# arduino.net
KiCad netlist of a schematic drawn in EAGLE
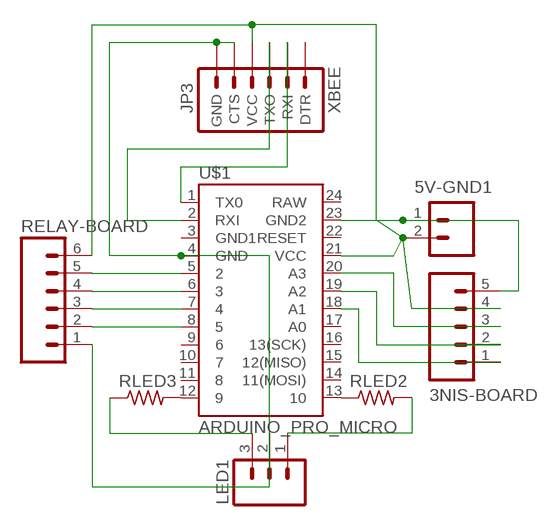
[diagram p0: schematic, sheet 1]

(export (version "E")
  (design (tool "Eeschema 10.0.6"))
  (components
    (comp (ref "3NIS-BOARD")
      (value "M05PTH")
      (footprint "eagle-import:1X05")
      (libsource (lib "eagle-import") (part "M05PTH"))
    )
    (comp (ref "5V-GND1")
      (value "M025MM")
      (footprint "eagle-import:SCREWTERMINAL-5MM-2")
      (libsource (lib "eagle-import") (part "M025MM"))
    )
    (comp (ref "JP3")
      (value "XBEE")
      (footprint "eagle-import:1X06")
      (libsource (lib "eagle-import") (part "ARDUINO_SERIAL_PROGRAMPTH"))
    )
    (comp (ref "LED1")
      (value "M03PTH")
      (footprint "eagle-import:1X03")
      (libsource (lib "eagle-import") (part "M03PTH"))
    )
    (comp (ref "RELAY-BOARD")
      (value "M06SIP")
      (footprint "eagle-import:1X06")
      (libsource (lib "eagle-import") (part "M06SIP"))
    )
    (comp (ref "RLED2")
      (value "R-US_M0805")
      (footprint "eagle-import:M0805")
      (libsource (lib "eagle-import") (part "R-US_M0805"))
    )
    (comp (ref "RLED3")
      (value "R-US_M0805")
      (footprint "eagle-import:M0805")
      (libsource (lib "eagle-import") (part "R-US_M0805"))
    )
    (comp (ref "U$1")
      (value "ARDUINO_PRO_MICRO")
      (footprint "eagle-import:ARDUINO_PRO_MICRO")
      (libsource (lib "eagle-import") (part "ARDUINO_PRO_MICRO"))
    )
  )
  (nets
    (net (code "1") (name "Net-(JP3-CTS)") (class "Default")
      (node (ref "JP3") (pin "5") (pinfunction "CTS_5") (pintype "passive"))
      (node (ref "JP3") (pin "6") (pinfunction "GND_6") (pintype "passive"))
      (node (ref "LED1") (pin "2") (pinfunction "2_2") (pintype "passive"))
      (node (ref "RELAY-BOARD") (pin "1") (pinfunction "1_1") (pintype "passive"))
      (node (ref "U$1") (pin "4") (pinfunction "GND_4") (pintype "bidirectional"))
    )
    (net (code "2") (name "Net-(JP3-RXI)") (class "Default")
      (node (ref "JP3") (pin "2") (pinfunction "RXI_2") (pintype "passive"))
      (node (ref "U$1") (pin "1") (pinfunction "TX0_1") (pintype "bidirectional"))
    )
    (net (code "3") (name "Net-(JP3-TXO)") (class "Default")
      (node (ref "JP3") (pin "3") (pinfunction "TXO_3") (pintype "passive"))
      (node (ref "U$1") (pin "2") (pinfunction "RXI_2") (pintype "bidirectional"))
    )
    (net (code "4") (name "Net-(JP3-VCC)") (class "Default")
      (node (ref "3NIS-BOARD") (pin "4") (pinfunction "4_4") (pintype "passive"))
      (node (ref "5V-GND1") (pin "2") (pinfunction "2_2") (pintype "passive"))
      (node (ref "JP3") (pin "4") (pinfunction "VCC_4") (pintype "passive"))
      (node (ref "RELAY-BOARD") (pin "6") (pinfunction "6_6") (pintype "passive"))
      (node (ref "U$1") (pin "21") (pinfunction "VCC_21") (pintype "bidirectional"))
    )
    (net (code "5") (name "Net-(LED1-Pad1)") (class "Default")
      (node (ref "LED1") (pin "1") (pinfunction "1_1") (pintype "passive"))
      (node (ref "RLED2") (pin "2") (pinfunction "2_2") (pintype "passive"))
    )
    (net (code "6") (name "Net-(LED1-Pad3)") (class "Default")
      (node (ref "LED1") (pin "3") (pinfunction "3_3") (pintype "passive"))
      (node (ref "RLED3") (pin "1") (pinfunction "1_1") (pintype "passive"))
    )
    (net (code "7") (name "Net-(U$1-2)") (class "Default")
      (node (ref "RELAY-BOARD") (pin "5") (pinfunction "5_5") (pintype "passive"))
      (node (ref "U$1") (pin "5") (pinfunction "2_5") (pintype "bidirectional"))
    )
    (net (code "8") (name "Net-(U$1-3)") (class "Default")
      (node (ref "RELAY-BOARD") (pin "4") (pinfunction "4_4") (pintype "passive"))
      (node (ref "U$1") (pin "6") (pinfunction "3_6") (pintype "bidirectional"))
    )
    (net (code "9") (name "Net-(U$1-4)") (class "Default")
      (node (ref "RELAY-BOARD") (pin "3") (pinfunction "3_3") (pintype "passive"))
      (node (ref "U$1") (pin "7") (pinfunction "4_7") (pintype "bidirectional"))
    )
    (net (code "10") (name "Net-(U$1-5)") (class "Default")
      (node (ref "RELAY-BOARD") (pin "2") (pinfunction "2_2") (pintype "passive"))
      (node (ref "U$1") (pin "8") (pinfunction "5_8") (pintype "bidirectional"))
    )
    (net (code "11") (name "Net-(U$1-9)") (class "Default")
      (node (ref "RLED3") (pin "2") (pinfunction "2_2") (pintype "passive"))
      (node (ref "U$1") (pin "12") (pinfunction "9_12") (pintype "bidirectional"))
    )
    (net (code "12") (name "Net-(U$1-10)") (class "Default")
      (node (ref "RLED2") (pin "1") (pinfunction "1_1") (pintype "passive"))
      (node (ref "U$1") (pin "13") (pinfunction "10_13") (pintype "bidirectional"))
    )
    (net (code "13") (name "Net-(U$1-A1)") (class "Default")
      (node (ref "3NIS-BOARD") (pin "1") (pinfunction "1_1") (pintype "passive"))
      (node (ref "U$1") (pin "18") (pinfunction "A1_18") (pintype "bidirectional"))
    )
    (net (code "14") (name "Net-(U$1-A2)") (class "Default")
      (node (ref "3NIS-BOARD") (pin "2") (pinfunction "2_2") (pintype "passive"))
      (node (ref "U$1") (pin "19") (pinfunction "A2_19") (pintype "bidirectional"))
    )
    (net (code "15") (name "Net-(U$1-A3)") (class "Default")
      (node (ref "3NIS-BOARD") (pin "3") (pinfunction "3_3") (pintype "passive"))
      (node (ref "U$1") (pin "20") (pinfunction "A3_20") (pintype "bidirectional"))
    )
    (net (code "16") (name "Net-(U$1-GND2)") (class "Default")
      (node (ref "3NIS-BOARD") (pin "5") (pinfunction "5_5") (pintype "passive"))
      (node (ref "5V-GND1") (pin "1") (pinfunction "1_1") (pintype "passive"))
      (node (ref "U$1") (pin "23") (pinfunction "GND2_23") (pintype "bidirectional"))
    )
    (net (code "17") (name "unconnected-(JP3-DTR-Pad1)") (class "Default")
      (node (ref "JP3") (pin "1") (pinfunction "DTR_1") (pintype "passive"))
    )
    (net (code "18") (name "unconnected-(U$1-6-Pad9)") (class "Default")
      (node (ref "U$1") (pin "9") (pinfunction "6_9") (pintype "bidirectional"))
    )
    (net (code "19") (name "unconnected-(U$1-7-Pad10)") (class "Default")
      (node (ref "U$1") (pin "10") (pinfunction "7_10") (pintype "bidirectional"))
    )
    (net (code "20") (name "unconnected-(U$1-8-Pad11)") (class "Default")
      (node (ref "U$1") (pin "11") (pinfunction "8_11") (pintype "bidirectional"))
    )
    (net (code "21") (name "unconnected-(U$1-11(MOSI)-Pad14)") (class "Default")
      (node (ref "U$1") (pin "14") (pinfunction "11(MOSI)_14") (pintype "bidirectional"))
    )
    (net (code "22") (name "unconnected-(U$1-12(MISO)-Pad15)") (class "Default")
      (node (ref "U$1") (pin "15") (pinfunction "12(MISO)_15") (pintype "bidirectional"))
    )
    (net (code "23") (name "unconnected-(U$1-13(SCK)-Pad16)") (class "Default")
      (node (ref "U$1") (pin "16") (pinfunction "13(SCK)_16") (pintype "bidirectional"))
    )
    (net (code "24") (name "unconnected-(U$1-A0-Pad17)") (class "Default")
      (node (ref "U$1") (pin "17") (pinfunction "A0_17") (pintype "bidirectional"))
    )
    (net (code "25") (name "unconnected-(U$1-GND1-Pad3)") (class "Default")
      (node (ref "U$1") (pin "3") (pinfunction "GND1_3") (pintype "bidirectional"))
    )
    (net (code "26") (name "unconnected-(U$1-RAW-Pad24)") (class "Default")
      (node (ref "U$1") (pin "24") (pinfunction "RAW_24") (pintype "bidirectional"))
    )
    (net (code "27") (name "unconnected-(U$1-RESET-Pad22)") (class "Default")
      (node (ref "U$1") (pin "22") (pinfunction "RESET_22") (pintype "bidirectional"))
    )
  )
)
